# fenrir.net
KiCad netlist of a schematic drawn in EAGLE
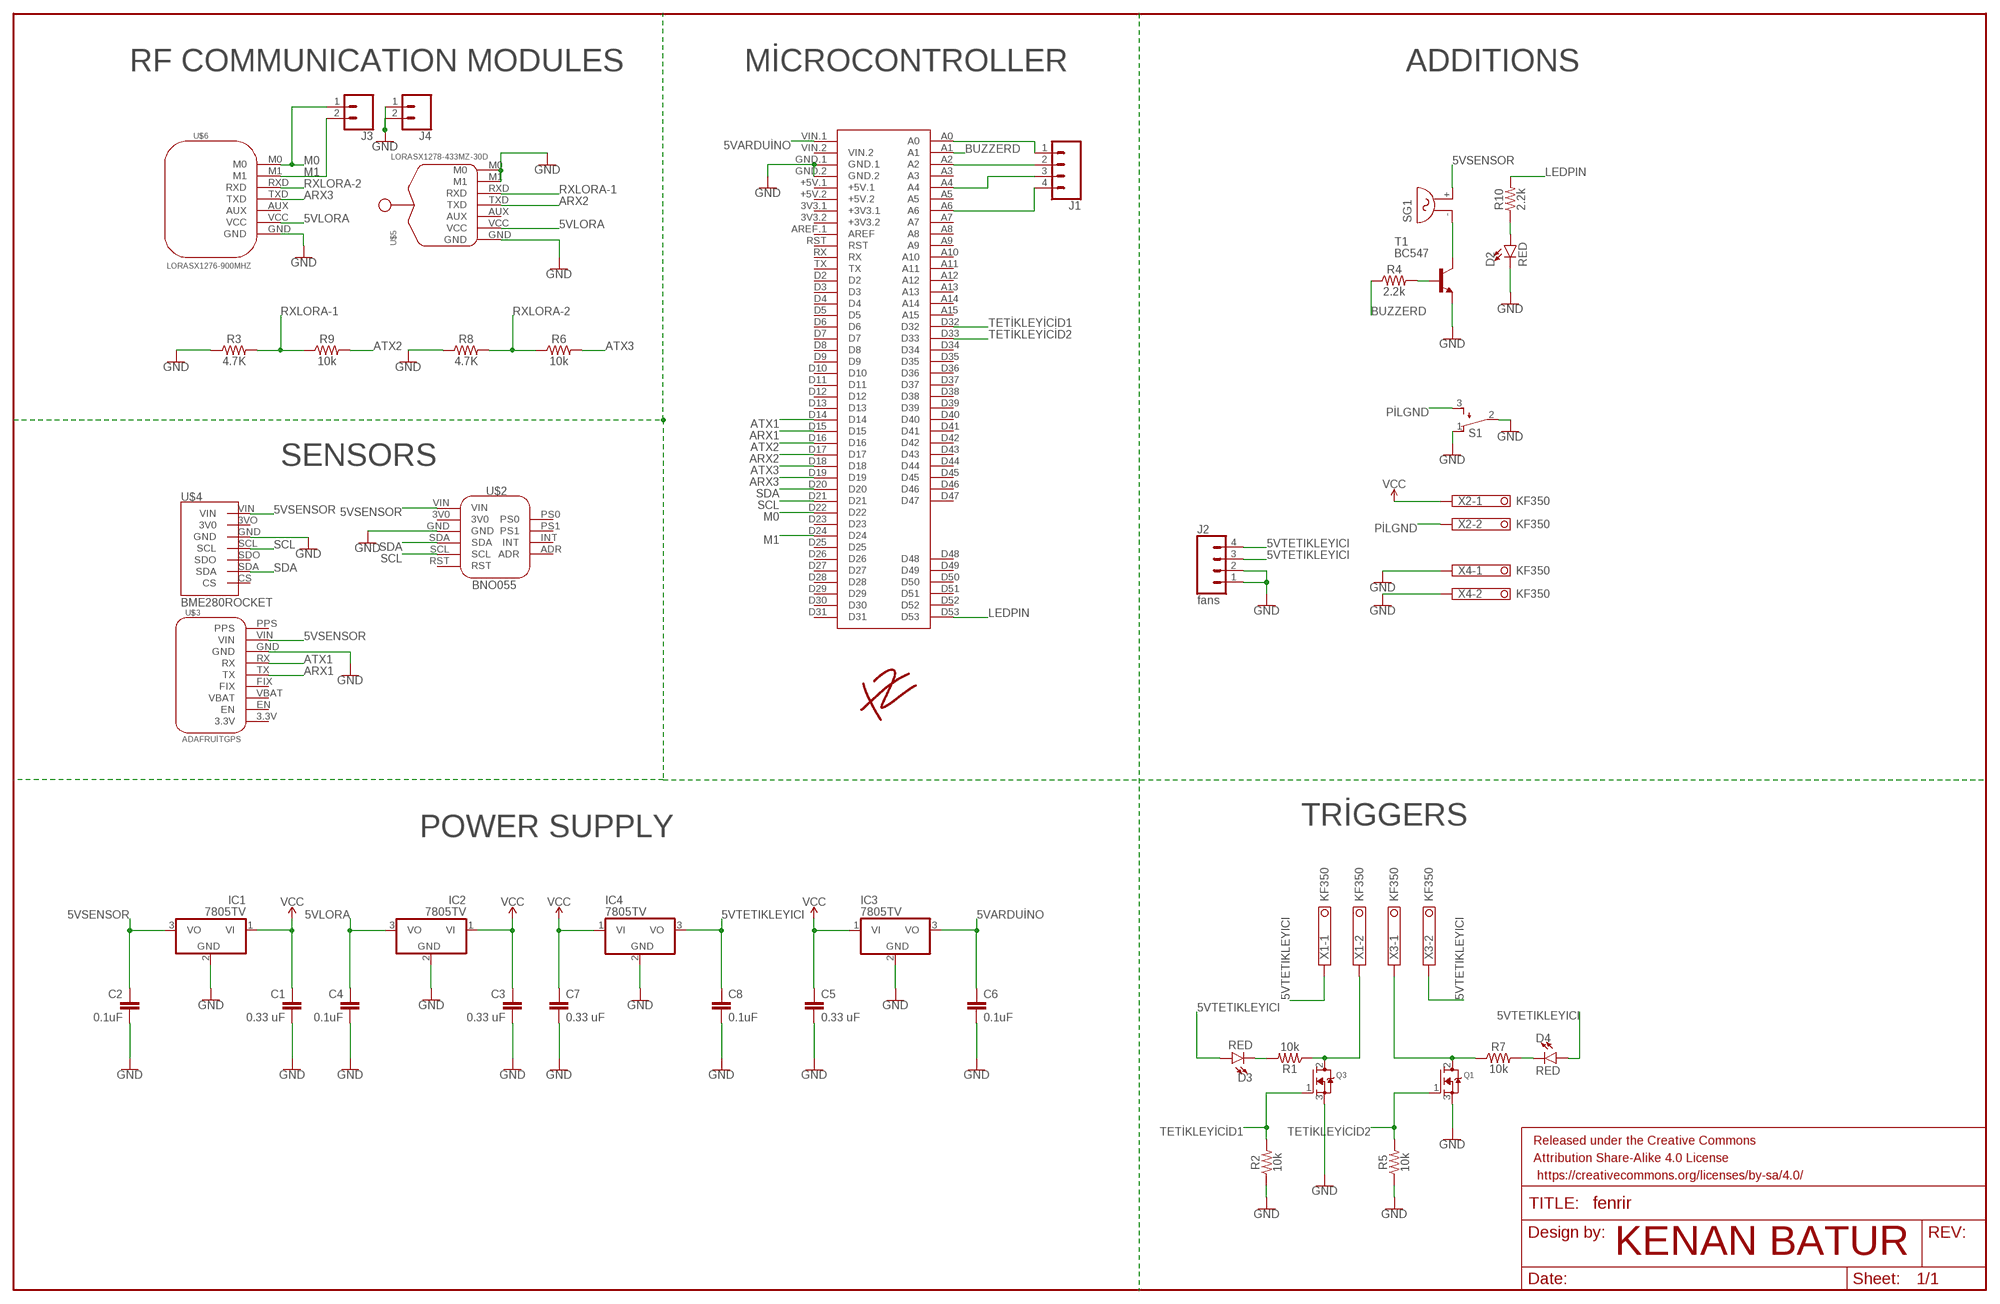
[diagram p0: schematic, sheet 1]

(export (version "E")
  (design (tool "Eeschema 10.0.6"))
  (components
    (comp (ref "C1")
      (value "0.33 uF")
      (footprint "eagle-import:C2.5-3")
      (libsource (lib "eagle-import") (part "C2,5-3"))
    )
    (comp (ref "C2")
      (value "0.1uF")
      (footprint "eagle-import:C2.5-3")
      (libsource (lib "eagle-import") (part "C2,5-3"))
    )
    (comp (ref "C3")
      (value "0.33 uF")
      (footprint "eagle-import:C2.5-3")
      (libsource (lib "eagle-import") (part "C2,5-3"))
    )
    (comp (ref "C4")
      (value "0.1uF")
      (footprint "eagle-import:C2.5-3")
      (libsource (lib "eagle-import") (part "C2,5-3"))
    )
    (comp (ref "C5")
      (value "0.33 uF")
      (footprint "eagle-import:C2.5-3")
      (libsource (lib "eagle-import") (part "C2,5-3"))
    )
    (comp (ref "C6")
      (value "0.1uF")
      (footprint "eagle-import:C2.5-3")
      (libsource (lib "eagle-import") (part "C2,5-3"))
    )
    (comp (ref "C7")
      (value "0.33 uF")
      (footprint "eagle-import:C2.5-3")
      (libsource (lib "eagle-import") (part "C2,5-3"))
    )
    (comp (ref "C8")
      (value "0.1uF")
      (footprint "eagle-import:C2.5-3")
      (libsource (lib "eagle-import") (part "C2,5-3"))
    )
    (comp (ref "D2")
      (value "RED")
      (footprint "eagle-import:LED-1206")
      (libsource (lib "eagle-import") (part "LED-RED1206"))
    )
    (comp (ref "D3")
      (value "RED")
      (footprint "eagle-import:LED-1206")
      (libsource (lib "eagle-import") (part "LED-RED1206"))
    )
    (comp (ref "D4")
      (value "RED")
      (footprint "eagle-import:LED-1206")
      (libsource (lib "eagle-import") (part "LED-RED1206"))
    )
    (comp (ref "FRAME2")
      (value "FRAME-LEDGER")
      (footprint "eagle-import:CREATIVE_COMMONS")
      (fields (field (name "DESIGN") "asd"))
      (libsource (lib "eagle-import") (part "FRAME-LEDGER"))
    )
    (comp (ref "IC1")
      (value "7805TV")
      (footprint "eagle-import:TO220V")
      (libsource (lib "eagle-import") (part "78TV05"))
    )
    (comp (ref "IC2")
      (value "7805TV")
      (footprint "eagle-import:TO220V")
      (libsource (lib "eagle-import") (part "78TV05"))
    )
    (comp (ref "IC3")
      (value "7805TV")
      (footprint "eagle-import:TO220V")
      (libsource (lib "eagle-import") (part "78TV05"))
    )
    (comp (ref "IC4")
      (value "7805TV")
      (footprint "eagle-import:TO220V")
      (libsource (lib "eagle-import") (part "78TV05"))
    )
    (comp (ref "J1")
      (value "CONN_04")
      (footprint "eagle-import:1X04")
      (libsource (lib "eagle-import") (part "CONN_04"))
    )
    (comp (ref "J2")
      (value "fans")
      (footprint "eagle-import:1X04")
      (libsource (lib "eagle-import") (part "CONN_04"))
    )
    (comp (ref "J3")
      (value "CONN_02")
      (footprint "eagle-import:1X02")
      (libsource (lib "eagle-import") (part "CONN_02"))
    )
    (comp (ref "J4")
      (value "CONN_02")
      (footprint "eagle-import:1X02")
      (libsource (lib "eagle-import") (part "CONN_02"))
    )
    (comp (ref "Q1")
      (value "MOSFET-NGDS_TO220V")
      (footprint "eagle-import:TO220V")
      (libsource (lib "eagle-import") (part "MOSFET-NGDS_TO220V"))
    )
    (comp (ref "Q3")
      (value "MOSFET-NGDS_TO220V")
      (footprint "eagle-import:TO220V")
      (libsource (lib "eagle-import") (part "MOSFET-NGDS_TO220V"))
    )
    (comp (ref "R1")
      (value "10k")
      (footprint "eagle-import:AXIAL-0.3")
      (libsource (lib "eagle-import") (part "10KOHM-HORIZ-1/4W-1%"))
    )
    (comp (ref "R2")
      (value "10k")
      (footprint "eagle-import:AXIAL-0.3")
      (libsource (lib "eagle-import") (part "10KOHM-HORIZ-1/4W-1%"))
    )
    (comp (ref "R3")
      (value "4.7K")
      (footprint "eagle-import:AXIAL-0.3")
      (libsource (lib "eagle-import") (part "10KOHM-HORIZ-1/4W-5%"))
    )
    (comp (ref "R4")
      (value "2.2k")
      (footprint "eagle-import:AXIAL-0.3")
      (libsource (lib "eagle-import") (part "10KOHM-HORIZ-1/4W-1%"))
    )
    (comp (ref "R5")
      (value "10k")
      (footprint "eagle-import:AXIAL-0.3")
      (libsource (lib "eagle-import") (part "10KOHM-HORIZ-1/4W-1%"))
    )
    (comp (ref "R6")
      (value "10k")
      (footprint "eagle-import:AXIAL-0.3")
      (libsource (lib "eagle-import") (part "10KOHM-HORIZ-1/4W-5%"))
    )
    (comp (ref "R7")
      (value "10k")
      (footprint "eagle-import:AXIAL-0.3")
      (libsource (lib "eagle-import") (part "10KOHM-HORIZ-1/4W-1%"))
    )
    (comp (ref "R8")
      (value "4.7K")
      (footprint "eagle-import:AXIAL-0.3")
      (libsource (lib "eagle-import") (part "10KOHM-HORIZ-1/4W-5%"))
    )
    (comp (ref "R9")
      (value "10k")
      (footprint "eagle-import:AXIAL-0.3")
      (libsource (lib "eagle-import") (part "10KOHM-HORIZ-1/4W-5%"))
    )
    (comp (ref "R10")
      (value "2.2k")
      (footprint "eagle-import:AXIAL-0.3")
      (libsource (lib "eagle-import") (part "10KOHM-HORIZ-1/4W-1%"))
    )
    (comp (ref "S1")
      (value "TL32PO")
      (footprint "eagle-import:TL3XPO")
      (libsource (lib "eagle-import") (part "TL32PO"))
    )
    (comp (ref "SG1")
      (value "F/QMX")
      (footprint "eagle-import:F_QMX")
      (libsource (lib "eagle-import") (part "F/QMX"))
    )
    (comp (ref "T1")
      (value "BC547")
      (footprint "eagle-import:TO92")
      (libsource (lib "eagle-import") (part "BC547"))
    )
    (comp (ref "U$1")
      (value "MEGA2560_MIKRO")
      (footprint "eagle-import:MEGA2560_MIKRO")
      (libsource (lib "eagle-import") (part "MEGA2560_MIKRO"))
    )
    (comp (ref "U$2")
      (value "BNO055")
      (footprint "eagle-import:BNO055")
      (libsource (lib "eagle-import") (part "BNO055"))
    )
    (comp (ref "U$3")
      (value "ADAFRUİTGPS")
      (footprint "eagle-import:ADAFRUİTGPS")
      (libsource (lib "eagle-import") (part "ADAFRUİTGPS"))
    )
    (comp (ref "U$4")
      (value "BME280ROCKET")
      (footprint "eagle-import:BME280ROCKET")
      (libsource (lib "eagle-import") (part "BME280ROCKET"))
    )
    (comp (ref "U$5")
      (value "LORASX1278-433MZ-30D")
      (footprint "eagle-import:LORASX1278-433MHZ-30D")
      (libsource (lib "eagle-import") (part "LORASX1278-433MZ-30D"))
    )
    (comp (ref "U$6")
      (value "LORASX1276-900MHZ")
      (footprint "eagle-import:LORASX1278-433MHZ")
      (libsource (lib "eagle-import") (part "LORASX1278-433MHZ"))
    )
    (comp (ref "U$7")
      (value "MAVİLOGO")
      (footprint "eagle-import:LOGOMAVİ")
      (libsource (lib "eagle-import") (part "MAVİLOGO"))
    )
    (comp (ref "X1")
      (value "KF350")
      (footprint "eagle-import:TERMINAL-BLOCK-2-PIN-3.5MM-ROUND-PAD")
      (libsource (lib "eagle-import") (part "TERMINAL-BLOCK-3.5MM-2-PIN-ROUND-PAD"))
    )
    (comp (ref "X2")
      (value "KF350")
      (footprint "eagle-import:TERMINAL-BLOCK-2-PIN-3.5MM-ROUND-PAD")
      (libsource (lib "eagle-import") (part "TERMINAL-BLOCK-3.5MM-2-PIN-ROUND-PAD"))
    )
    (comp (ref "X3")
      (value "KF350")
      (footprint "eagle-import:TERMINAL-BLOCK-2-PIN-3.5MM-ROUND-PAD")
      (libsource (lib "eagle-import") (part "TERMINAL-BLOCK-3.5MM-2-PIN-ROUND-PAD"))
    )
    (comp (ref "X4")
      (value "KF350")
      (footprint "eagle-import:TERMINAL-BLOCK-2-PIN-3.5MM-ROUND-PAD")
      (libsource (lib "eagle-import") (part "TERMINAL-BLOCK-3.5MM-2-PIN-ROUND-PAD"))
    )
  )
  (nets
    (net (code "1") (name "/5VARDUİNO") (class "Default")
      (node (ref "C6") (pin "1") (pinfunction "1_1") (pintype "passive"))
      (node (ref "IC3") (pin "3") (pinfunction "VO_3") (pintype "passive"))
      (node (ref "U$1") (pin "VIN.1") (pinfunction "VIN.1_VIN.1") (pintype "bidirectional"))
    )
    (net (code "2") (name "/5VLORA") (class "Default")
      (node (ref "C4") (pin "1") (pinfunction "1_1") (pintype "passive"))
      (node (ref "IC2") (pin "3") (pinfunction "VO_3") (pintype "passive"))
      (node (ref "U$5") (pin "VCC") (pinfunction "VCC_VCC") (pintype "bidirectional"))
      (node (ref "U$6") (pin "VCC") (pinfunction "VCC_VCC") (pintype "bidirectional"))
    )
    (net (code "3") (name "/5VSENSOR") (class "Default")
      (node (ref "C2") (pin "1") (pinfunction "1_1") (pintype "passive"))
      (node (ref "IC1") (pin "3") (pinfunction "VO_3") (pintype "passive"))
      (node (ref "SG1") (pin "+") (pinfunction "2_+") (pintype "passive"))
      (node (ref "U$2") (pin "VIN") (pinfunction "VIN_VIN") (pintype "bidirectional"))
      (node (ref "U$3") (pin "VIN") (pinfunction "VIN_VIN") (pintype "bidirectional"))
      (node (ref "U$4") (pin "VIN") (pinfunction "VIN_VIN") (pintype "bidirectional"))
    )
    (net (code "4") (name "/5VTETIKLEYICI") (class "Default")
      (node (ref "C8") (pin "1") (pinfunction "1_1") (pintype "passive"))
      (node (ref "D3") (pin "A") (pinfunction "A_A") (pintype "passive"))
      (node (ref "D4") (pin "A") (pinfunction "A_A") (pintype "passive"))
      (node (ref "IC4") (pin "3") (pinfunction "VO_3") (pintype "passive"))
      (node (ref "J2") (pin "3") (pinfunction "3_3") (pintype "passive"))
      (node (ref "J2") (pin "4") (pinfunction "4_4") (pintype "passive"))
      (node (ref "X1") (pin "1") (pinfunction "K_1") (pintype "passive"))
      (node (ref "X3") (pin "2") (pinfunction "K_2") (pintype "passive"))
    )
    (net (code "5") (name "/ARX1") (class "Default")
      (node (ref "U$1") (pin "D15") (pinfunction "D15_D15") (pintype "bidirectional"))
      (node (ref "U$3") (pin "TX") (pinfunction "TX_TX") (pintype "bidirectional"))
    )
    (net (code "6") (name "/ARX2") (class "Default")
      (node (ref "U$1") (pin "D17") (pinfunction "D17_D17") (pintype "bidirectional"))
      (node (ref "U$5") (pin "TXD") (pinfunction "TXD_TXD") (pintype "bidirectional"))
    )
    (net (code "7") (name "/ARX3") (class "Default")
      (node (ref "U$1") (pin "D19") (pinfunction "D19_D19") (pintype "bidirectional"))
      (node (ref "U$6") (pin "TXD") (pinfunction "TXD_TXD") (pintype "bidirectional"))
    )
    (net (code "8") (name "/ATX1") (class "Default")
      (node (ref "U$1") (pin "D14") (pinfunction "D14_D14") (pintype "bidirectional"))
      (node (ref "U$3") (pin "RX") (pinfunction "RX_RX") (pintype "bidirectional"))
    )
    (net (code "9") (name "/ATX2") (class "Default")
      (node (ref "R9") (pin "P$2") (pinfunction "2_P$2") (pintype "passive"))
      (node (ref "U$1") (pin "D16") (pinfunction "D16_D16") (pintype "bidirectional"))
    )
    (net (code "10") (name "/ATX3") (class "Default")
      (node (ref "R6") (pin "P$2") (pinfunction "2_P$2") (pintype "passive"))
      (node (ref "U$1") (pin "D18") (pinfunction "D18_D18") (pintype "bidirectional"))
    )
    (net (code "11") (name "/BUZZERD") (class "Default")
      (node (ref "R4") (pin "P$1") (pinfunction "1_P$1") (pintype "passive"))
      (node (ref "U$1") (pin "A1") (pinfunction "A1_A1") (pintype "bidirectional"))
    )
    (net (code "12") (name "/LEDPIN") (class "Default")
      (node (ref "R10") (pin "P$2") (pinfunction "2_P$2") (pintype "passive"))
      (node (ref "U$1") (pin "D53") (pinfunction "D53_D53") (pintype "bidirectional"))
    )
    (net (code "13") (name "/M0") (class "Default")
      (node (ref "J3") (pin "1") (pinfunction "1_1") (pintype "passive"))
      (node (ref "U$1") (pin "D22") (pinfunction "D22_D22") (pintype "bidirectional"))
      (node (ref "U$6") (pin "M0") (pinfunction "M0_M0") (pintype "bidirectional"))
    )
    (net (code "14") (name "/M1") (class "Default")
      (node (ref "J3") (pin "2") (pinfunction "2_2") (pintype "passive"))
      (node (ref "U$1") (pin "D24") (pinfunction "D24_D24") (pintype "bidirectional"))
      (node (ref "U$6") (pin "M1") (pinfunction "M1_M1") (pintype "bidirectional"))
    )
    (net (code "15") (name "/PİLGND") (class "Default")
      (node (ref "S1") (pin "3") (pinfunction "S_3") (pintype "passive"))
      (node (ref "X2") (pin "2") (pinfunction "K_2") (pintype "passive"))
    )
    (net (code "16") (name "/RXLORA-1") (class "Default")
      (node (ref "R3") (pin "P$2") (pinfunction "2_P$2") (pintype "passive"))
      (node (ref "R9") (pin "P$1") (pinfunction "1_P$1") (pintype "passive"))
      (node (ref "U$5") (pin "RXD") (pinfunction "RXD_RXD") (pintype "bidirectional"))
    )
    (net (code "17") (name "/RXLORA-2") (class "Default")
      (node (ref "R6") (pin "P$1") (pinfunction "1_P$1") (pintype "passive"))
      (node (ref "R8") (pin "P$2") (pinfunction "2_P$2") (pintype "passive"))
      (node (ref "U$6") (pin "RXD") (pinfunction "RXD_RXD") (pintype "bidirectional"))
    )
    (net (code "18") (name "/SCL") (class "Default")
      (node (ref "U$1") (pin "D21") (pinfunction "D21_D21") (pintype "bidirectional"))
      (node (ref "U$2") (pin "SCL") (pinfunction "SCL_SCL") (pintype "bidirectional"))
      (node (ref "U$4") (pin "SCL") (pinfunction "SCL_SCL") (pintype "bidirectional"))
    )
    (net (code "19") (name "/SDA") (class "Default")
      (node (ref "U$1") (pin "D20") (pinfunction "D20_D20") (pintype "bidirectional"))
      (node (ref "U$2") (pin "SDA") (pinfunction "SDA_SDA") (pintype "bidirectional"))
      (node (ref "U$4") (pin "SDA") (pinfunction "SDA_SDA") (pintype "bidirectional"))
    )
    (net (code "20") (name "/TETİKLEYİCİD1") (class "Default")
      (node (ref "Q3") (pin "1") (pinfunction "G_1") (pintype "bidirectional"))
      (node (ref "R2") (pin "P$2") (pinfunction "2_P$2") (pintype "passive"))
      (node (ref "U$1") (pin "D32") (pinfunction "D32_D32") (pintype "bidirectional"))
    )
    (net (code "21") (name "/TETİKLEYİCİD2") (class "Default")
      (node (ref "Q1") (pin "1") (pinfunction "G_1") (pintype "bidirectional"))
      (node (ref "R5") (pin "P$2") (pinfunction "2_P$2") (pintype "passive"))
      (node (ref "U$1") (pin "D33") (pinfunction "D33_D33") (pintype "bidirectional"))
    )
    (net (code "22") (name "GND") (class "Default")
      (node (ref "C1") (pin "2") (pinfunction "2_2") (pintype "passive"))
      (node (ref "C2") (pin "2") (pinfunction "2_2") (pintype "passive"))
      (node (ref "C3") (pin "2") (pinfunction "2_2") (pintype "passive"))
      (node (ref "C4") (pin "2") (pinfunction "2_2") (pintype "passive"))
      (node (ref "C5") (pin "2") (pinfunction "2_2") (pintype "passive"))
      (node (ref "C6") (pin "2") (pinfunction "2_2") (pintype "passive"))
      (node (ref "C7") (pin "2") (pinfunction "2_2") (pintype "passive"))
      (node (ref "C8") (pin "2") (pinfunction "2_2") (pintype "passive"))
      (node (ref "D2") (pin "C") (pinfunction "C_C") (pintype "passive"))
      (node (ref "IC1") (pin "2") (pinfunction "GND_2") (pintype "passive"))
      (node (ref "IC2") (pin "2") (pinfunction "GND_2") (pintype "passive"))
      (node (ref "IC3") (pin "2") (pinfunction "GND_2") (pintype "passive"))
      (node (ref "IC4") (pin "2") (pinfunction "GND_2") (pintype "passive"))
      (node (ref "J2") (pin "1") (pinfunction "1_1") (pintype "passive"))
      (node (ref "J2") (pin "2") (pinfunction "2_2") (pintype "passive"))
      (node (ref "J4") (pin "1") (pinfunction "1_1") (pintype "passive"))
      (node (ref "J4") (pin "2") (pinfunction "2_2") (pintype "passive"))
      (node (ref "Q1") (pin "3") (pinfunction "S_3") (pintype "bidirectional"))
      (node (ref "Q3") (pin "3") (pinfunction "S_3") (pintype "bidirectional"))
      (node (ref "R2") (pin "P$1") (pinfunction "1_P$1") (pintype "passive"))
      (node (ref "R3") (pin "P$1") (pinfunction "1_P$1") (pintype "passive"))
      (node (ref "R5") (pin "P$1") (pinfunction "1_P$1") (pintype "passive"))
      (node (ref "R8") (pin "P$1") (pinfunction "1_P$1") (pintype "passive"))
      (node (ref "S1") (pin "1") (pinfunction "O_1") (pintype "passive"))
      (node (ref "S1") (pin "2") (pinfunction "P_2") (pintype "passive"))
      (node (ref "T1") (pin "1") (pinfunction "E_1") (pintype "passive"))
      (node (ref "U$1") (pin "GND.1") (pinfunction "GND.1_GND.1") (pintype "bidirectional"))
      (node (ref "U$1") (pin "GND.2") (pinfunction "GND.2_GND.2") (pintype "bidirectional"))
      (node (ref "U$2") (pin "GND") (pinfunction "GND_GND") (pintype "bidirectional"))
      (node (ref "U$3") (pin "GND") (pinfunction "GND_GND") (pintype "bidirectional"))
      (node (ref "U$4") (pin "GND") (pinfunction "GND_GND") (pintype "bidirectional"))
      (node (ref "U$5") (pin "GND") (pinfunction "GND_GND") (pintype "bidirectional"))
      (node (ref "U$5") (pin "M0") (pinfunction "M0_M0") (pintype "bidirectional"))
      (node (ref "U$5") (pin "M1") (pinfunction "M1_M1") (pintype "bidirectional"))
      (node (ref "U$6") (pin "GND") (pinfunction "GND_GND") (pintype "bidirectional"))
      (node (ref "X4") (pin "1") (pinfunction "K_1") (pintype "passive"))
      (node (ref "X4") (pin "2") (pinfunction "K_2") (pintype "passive"))
    )
    (net (code "23") (name "Net-(J1-Pad1)") (class "Default")
      (node (ref "J1") (pin "1") (pinfunction "1_1") (pintype "passive"))
      (node (ref "U$1") (pin "A0") (pinfunction "A0_A0") (pintype "bidirectional"))
    )
    (net (code "24") (name "Net-(J1-Pad2)") (class "Default")
      (node (ref "J1") (pin "2") (pinfunction "2_2") (pintype "passive"))
      (node (ref "U$1") (pin "A2") (pinfunction "A2_A2") (pintype "bidirectional"))
    )
    (net (code "25") (name "Net-(J1-Pad3)") (class "Default")
      (node (ref "J1") (pin "3") (pinfunction "3_3") (pintype "passive"))
      (node (ref "U$1") (pin "A4") (pinfunction "A4_A4") (pintype "bidirectional"))
    )
    (net (code "26") (name "Net-(J1-Pad4)") (class "Default")
      (node (ref "J1") (pin "4") (pinfunction "4_4") (pintype "passive"))
      (node (ref "U$1") (pin "A6") (pinfunction "A6_A6") (pintype "bidirectional"))
    )
    (net (code "27") (name "Net-(Q1-D)") (class "Default")
      (node (ref "Q1") (pin "2") (pinfunction "D_2") (pintype "bidirectional"))
      (node (ref "R7") (pin "P$1") (pinfunction "1_P$1") (pintype "passive"))
      (node (ref "X3") (pin "1") (pinfunction "K_1") (pintype "passive"))
    )
    (net (code "28") (name "Net-(Q3-D)") (class "Default")
      (node (ref "Q3") (pin "2") (pinfunction "D_2") (pintype "bidirectional"))
      (node (ref "R1") (pin "P$1") (pinfunction "1_P$1") (pintype "passive"))
      (node (ref "X1") (pin "2") (pinfunction "K_2") (pintype "passive"))
    )
    (net (code "29") (name "Net-(R1-2)") (class "Default")
      (node (ref "D3") (pin "C") (pinfunction "C_C") (pintype "passive"))
      (node (ref "R1") (pin "P$2") (pinfunction "2_P$2") (pintype "passive"))
    )
    (net (code "30") (name "Net-(R4-2)") (class "Default")
      (node (ref "R4") (pin "P$2") (pinfunction "2_P$2") (pintype "passive"))
      (node (ref "T1") (pin "2") (pinfunction "B_2") (pintype "passive"))
    )
    (net (code "31") (name "Net-(R7-2)") (class "Default")
      (node (ref "D4") (pin "C") (pinfunction "C_C") (pintype "passive"))
      (node (ref "R7") (pin "P$2") (pinfunction "2_P$2") (pintype "passive"))
    )
    (net (code "32") (name "Net-(R10-1)") (class "Default")
      (node (ref "D2") (pin "A") (pinfunction "A_A") (pintype "passive"))
      (node (ref "R10") (pin "P$1") (pinfunction "1_P$1") (pintype "passive"))
    )
    (net (code "33") (name "Net-(SG1-1)") (class "Default")
      (node (ref "SG1") (pin "-") (pinfunction "1_-") (pintype "passive"))
      (node (ref "T1") (pin "3") (pinfunction "C_3") (pintype "passive"))
    )
    (net (code "34") (name "VCC") (class "Default")
      (node (ref "C1") (pin "1") (pinfunction "1_1") (pintype "passive"))
      (node (ref "C3") (pin "1") (pinfunction "1_1") (pintype "passive"))
      (node (ref "C5") (pin "1") (pinfunction "1_1") (pintype "passive"))
      (node (ref "C7") (pin "1") (pinfunction "1_1") (pintype "passive"))
      (node (ref "IC1") (pin "1") (pinfunction "VI_1") (pintype "input"))
      (node (ref "IC2") (pin "1") (pinfunction "VI_1") (pintype "input"))
      (node (ref "IC3") (pin "1") (pinfunction "VI_1") (pintype "input"))
      (node (ref "IC4") (pin "1") (pinfunction "VI_1") (pintype "input"))
      (node (ref "X2") (pin "1") (pinfunction "K_1") (pintype "passive"))
    )
    (net (code "35") (name "unconnected-(U$1-+3V3.1-Pad3V3.1)") (class "Default")
      (node (ref "U$1") (pin "3V3.1") (pinfunction "+3V3.1_3V3.1") (pintype "bidirectional"))
    )
    (net (code "36") (name "unconnected-(U$1-+3V3.2-Pad3V3.2)") (class "Default")
      (node (ref "U$1") (pin "3V3.2") (pinfunction "+3V3.2_3V3.2") (pintype "bidirectional"))
    )
    (net (code "37") (name "unconnected-(U$1-AREF-PadAREF.1)") (class "Default")
      (node (ref "U$1") (pin "AREF.1") (pinfunction "AREF_AREF.1") (pintype "bidirectional"))
    )
    (net (code "38") (name "unconnected-(U$1-Pad+5V.1)") (class "Default")
      (node (ref "U$1") (pin "+5V.1") (pinfunction "+5V.1_+5V.1") (pintype "bidirectional"))
    )
    (net (code "39") (name "unconnected-(U$1-Pad+5V.2)") (class "Default")
      (node (ref "U$1") (pin "+5V.2") (pinfunction "+5V.2_+5V.2") (pintype "bidirectional"))
    )
    (net (code "40") (name "unconnected-(U$1-PadA3)") (class "Default")
      (node (ref "U$1") (pin "A3") (pinfunction "A3_A3") (pintype "bidirectional"))
    )
    (net (code "41") (name "unconnected-(U$1-PadA5)") (class "Default")
      (node (ref "U$1") (pin "A5") (pinfunction "A5_A5") (pintype "bidirectional"))
    )
    (net (code "42") (name "unconnected-(U$1-PadA7)") (class "Default")
      (node (ref "U$1") (pin "A7") (pinfunction "A7_A7") (pintype "bidirectional"))
    )
    (net (code "43") (name "unconnected-(U$1-PadA8)") (class "Default")
      (node (ref "U$1") (pin "A8") (pinfunction "A8_A8") (pintype "bidirectional"))
    )
    (net (code "44") (name "unconnected-(U$1-PadA9)") (class "Default")
      (node (ref "U$1") (pin "A9") (pinfunction "A9_A9") (pintype "bidirectional"))
    )
    (net (code "45") (name "unconnected-(U$1-PadA10)") (class "Default")
      (node (ref "U$1") (pin "A10") (pinfunction "A10_A10") (pintype "bidirectional"))
    )
    (net (code "46") (name "unconnected-(U$1-PadA11)") (class "Default")
      (node (ref "U$1") (pin "A11") (pinfunction "A11_A11") (pintype "bidirectional"))
    )
    (net (code "47") (name "unconnected-(U$1-PadA12)") (class "Default")
      (node (ref "U$1") (pin "A12") (pinfunction "A12_A12") (pintype "bidirectional"))
    )
    (net (code "48") (name "unconnected-(U$1-PadA13)") (class "Default")
      (node (ref "U$1") (pin "A13") (pinfunction "A13_A13") (pintype "bidirectional"))
    )
    (net (code "49") (name "unconnected-(U$1-PadA14)") (class "Default")
      (node (ref "U$1") (pin "A14") (pinfunction "A14_A14") (pintype "bidirectional"))
    )
    (net (code "50") (name "unconnected-(U$1-PadA15)") (class "Default")
      (node (ref "U$1") (pin "A15") (pinfunction "A15_A15") (pintype "bidirectional"))
    )
    (net (code "51") (name "unconnected-(U$1-PadD2)") (class "Default")
      (node (ref "U$1") (pin "D2") (pinfunction "D2_D2") (pintype "bidirectional"))
    )
    (net (code "52") (name "unconnected-(U$1-PadD3)") (class "Default")
      (node (ref "U$1") (pin "D3") (pinfunction "D3_D3") (pintype "bidirectional"))
    )
    (net (code "53") (name "unconnected-(U$1-PadD4)") (class "Default")
      (node (ref "U$1") (pin "D4") (pinfunction "D4_D4") (pintype "bidirectional"))
    )
    (net (code "54") (name "unconnected-(U$1-PadD5)") (class "Default")
      (node (ref "U$1") (pin "D5") (pinfunction "D5_D5") (pintype "bidirectional"))
    )
    (net (code "55") (name "unconnected-(U$1-PadD6)") (class "Default")
      (node (ref "U$1") (pin "D6") (pinfunction "D6_D6") (pintype "bidirectional"))
    )
    (net (code "56") (name "unconnected-(U$1-PadD7)") (class "Default")
      (node (ref "U$1") (pin "D7") (pinfunction "D7_D7") (pintype "bidirectional"))
    )
    (net (code "57") (name "unconnected-(U$1-PadD8)") (class "Default")
      (node (ref "U$1") (pin "D8") (pinfunction "D8_D8") (pintype "bidirectional"))
    )
    (net (code "58") (name "unconnected-(U$1-PadD9)") (class "Default")
      (node (ref "U$1") (pin "D9") (pinfunction "D9_D9") (pintype "bidirectional"))
    )
    (net (code "59") (name "unconnected-(U$1-PadD10)") (class "Default")
      (node (ref "U$1") (pin "D10") (pinfunction "D10_D10") (pintype "bidirectional"))
    )
    (net (code "60") (name "unconnected-(U$1-PadD11)") (class "Default")
      (node (ref "U$1") (pin "D11") (pinfunction "D11_D11") (pintype "bidirectional"))
    )
    (net (code "61") (name "unconnected-(U$1-PadD12)") (class "Default")
      (node (ref "U$1") (pin "D12") (pinfunction "D12_D12") (pintype "bidirectional"))
    )
    (net (code "62") (name "unconnected-(U$1-PadD13)") (class "Default")
      (node (ref "U$1") (pin "D13") (pinfunction "D13_D13") (pintype "bidirectional"))
    )
    (net (code "63") (name "unconnected-(U$1-PadD23)") (class "Default")
      (node (ref "U$1") (pin "D23") (pinfunction "D23_D23") (pintype "bidirectional"))
    )
    (net (code "64") (name "unconnected-(U$1-PadD25)") (class "Default")
      (node (ref "U$1") (pin "D25") (pinfunction "D25_D25") (pintype "bidirectional"))
    )
    (net (code "65") (name "unconnected-(U$1-PadD26)") (class "Default")
      (node (ref "U$1") (pin "D26") (pinfunction "D26_D26") (pintype "bidirectional"))
    )
    (net (code "66") (name "unconnected-(U$1-PadD27)") (class "Default")
      (node (ref "U$1") (pin "D27") (pinfunction "D27_D27") (pintype "bidirectional"))
    )
    (net (code "67") (name "unconnected-(U$1-PadD28)") (class "Default")
      (node (ref "U$1") (pin "D28") (pinfunction "D28_D28") (pintype "bidirectional"))
    )
    (net (code "68") (name "unconnected-(U$1-PadD29)") (class "Default")
      (node (ref "U$1") (pin "D29") (pinfunction "D29_D29") (pintype "bidirectional"))
    )
    (net (code "69") (name "unconnected-(U$1-PadD30)") (class "Default")
      (node (ref "U$1") (pin "D30") (pinfunction "D30_D30") (pintype "bidirectional"))
    )
    (net (code "70") (name "unconnected-(U$1-PadD31)") (class "Default")
      (node (ref "U$1") (pin "D31") (pinfunction "D31_D31") (pintype "bidirectional"))
    )
    (net (code "71") (name "unconnected-(U$1-PadD34)") (class "Default")
      (node (ref "U$1") (pin "D34") (pinfunction "D34_D34") (pintype "bidirectional"))
    )
    (net (code "72") (name "unconnected-(U$1-PadD35)") (class "Default")
      (node (ref "U$1") (pin "D35") (pinfunction "D35_D35") (pintype "bidirectional"))
    )
    (net (code "73") (name "unconnected-(U$1-PadD36)") (class "Default")
      (node (ref "U$1") (pin "D36") (pinfunction "D36_D36") (pintype "bidirectional"))
    )
    (net (code "74") (name "unconnected-(U$1-PadD37)") (class "Default")
      (node (ref "U$1") (pin "D37") (pinfunction "D37_D37") (pintype "bidirectional"))
    )
    (net (code "75") (name "unconnected-(U$1-PadD38)") (class "Default")
      (node (ref "U$1") (pin "D38") (pinfunction "D38_D38") (pintype "bidirectional"))
    )
    (net (code "76") (name "unconnected-(U$1-PadD39)") (class "Default")
      (node (ref "U$1") (pin "D39") (pinfunction "D39_D39") (pintype "bidirectional"))
    )
    (net (code "77") (name "unconnected-(U$1-PadD40)") (class "Default")
      (node (ref "U$1") (pin "D40") (pinfunction "D40_D40") (pintype "bidirectional"))
    )
    (net (code "78") (name "unconnected-(U$1-PadD41)") (class "Default")
      (node (ref "U$1") (pin "D41") (pinfunction "D41_D41") (pintype "bidirectional"))
    )
    (net (code "79") (name "unconnected-(U$1-PadD42)") (class "Default")
      (node (ref "U$1") (pin "D42") (pinfunction "D42_D42") (pintype "bidirectional"))
    )
    (net (code "80") (name "unconnected-(U$1-PadD43)") (class "Default")
      (node (ref "U$1") (pin "D43") (pinfunction "D43_D43") (pintype "bidirectional"))
    )
    (net (code "81") (name "unconnected-(U$1-PadD44)") (class "Default")
      (node (ref "U$1") (pin "D44") (pinfunction "D44_D44") (pintype "bidirectional"))
    )
    (net (code "82") (name "unconnected-(U$1-PadD45)") (class "Default")
      (node (ref "U$1") (pin "D45") (pinfunction "D45_D45") (pintype "bidirectional"))
    )
    (net (code "83") (name "unconnected-(U$1-PadD46)") (class "Default")
      (node (ref "U$1") (pin "D46") (pinfunction "D46_D46") (pintype "bidirectional"))
    )
    (net (code "84") (name "unconnected-(U$1-PadD47)") (class "Default")
      (node (ref "U$1") (pin "D47") (pinfunction "D47_D47") (pintype "bidirectional"))
    )
    (net (code "85") (name "unconnected-(U$1-PadD48)") (class "Default")
      (node (ref "U$1") (pin "D48") (pinfunction "D48_D48") (pintype "bidirectional"))
    )
    (net (code "86") (name "unconnected-(U$1-PadD49)") (class "Default")
      (node (ref "U$1") (pin "D49") (pinfunction "D49_D49") (pintype "bidirectional"))
    )
    (net (code "87") (name "unconnected-(U$1-PadD50)") (class "Default")
      (node (ref "U$1") (pin "D50") (pinfunction "D50_D50") (pintype "bidirectional"))
    )
    (net (code "88") (name "unconnected-(U$1-PadD51)") (class "Default")
      (node (ref "U$1") (pin "D51") (pinfunction "D51_D51") (pintype "bidirectional"))
    )
    (net (code "89") (name "unconnected-(U$1-PadD52)") (class "Default")
      (node (ref "U$1") (pin "D52") (pinfunction "D52_D52") (pintype "bidirectional"))
    )
    (net (code "90") (name "unconnected-(U$1-PadRST)") (class "Default")
      (node (ref "U$1") (pin "RST") (pinfunction "RST_RST") (pintype "bidirectional"))
    )
    (net (code "91") (name "unconnected-(U$1-PadRX)") (class "Default")
      (node (ref "U$1") (pin "RX") (pinfunction "RX_RX") (pintype "bidirectional"))
    )
    (net (code "92") (name "unconnected-(U$1-PadTX)") (class "Default")
      (node (ref "U$1") (pin "TX") (pinfunction "TX_TX") (pintype "bidirectional"))
    )
    (net (code "93") (name "unconnected-(U$1-PadVIN.2)") (class "Default")
      (node (ref "U$1") (pin "VIN.2") (pinfunction "VIN.2_VIN.2") (pintype "bidirectional"))
    )
    (net (code "94") (name "unconnected-(U$2-Pad3V0)") (class "Default")
      (node (ref "U$2") (pin "3V0") (pinfunction "3V0_3V0") (pintype "bidirectional"))
    )
    (net (code "95") (name "unconnected-(U$2-PadADR)") (class "Default")
      (node (ref "U$2") (pin "ADR") (pinfunction "ADR_ADR") (pintype "bidirectional"))
    )
    (net (code "96") (name "unconnected-(U$2-PadINT)") (class "Default")
      (node (ref "U$2") (pin "INT") (pinfunction "INT_INT") (pintype "bidirectional"))
    )
    (net (code "97") (name "unconnected-(U$2-PadPS0)") (class "Default")
      (node (ref "U$2") (pin "PS0") (pinfunction "PS0_PS0") (pintype "bidirectional"))
    )
    (net (code "98") (name "unconnected-(U$2-PadPS1)") (class "Default")
      (node (ref "U$2") (pin "PS1") (pinfunction "PS1_PS1") (pintype "bidirectional"))
    )
    (net (code "99") (name "unconnected-(U$2-PadRST)") (class "Default")
      (node (ref "U$2") (pin "RST") (pinfunction "RST_RST") (pintype "bidirectional"))
    )
    (net (code "100") (name "unconnected-(U$3-Pad3.3V)") (class "Default")
      (node (ref "U$3") (pin "3.3V") (pinfunction "3.3V_3.3V") (pintype "bidirectional"))
    )
    (net (code "101") (name "unconnected-(U$3-PadEN)") (class "Default")
      (node (ref "U$3") (pin "EN") (pinfunction "EN_EN") (pintype "bidirectional"))
    )
    (net (code "102") (name "unconnected-(U$3-PadFIX)") (class "Default")
      (node (ref "U$3") (pin "FIX") (pinfunction "FIX_FIX") (pintype "bidirectional"))
    )
    (net (code "103") (name "unconnected-(U$3-PadPPS)") (class "Default")
      (node (ref "U$3") (pin "PPS") (pinfunction "PPS_PPS") (pintype "bidirectional"))
    )
    (net (code "104") (name "unconnected-(U$3-PadVBAT)") (class "Default")
      (node (ref "U$3") (pin "VBAT") (pinfunction "VBAT_VBAT") (pintype "bidirectional"))
    )
    (net (code "105") (name "unconnected-(U$4-3V0-Pad3VO)") (class "Default")
      (node (ref "U$4") (pin "3VO") (pinfunction "3V0_3VO") (pintype "bidirectional"))
    )
    (net (code "106") (name "unconnected-(U$4-PadCS)") (class "Default")
      (node (ref "U$4") (pin "CS") (pinfunction "CS_CS") (pintype "bidirectional"))
    )
    (net (code "107") (name "unconnected-(U$4-PadSDO)") (class "Default")
      (node (ref "U$4") (pin "SDO") (pinfunction "SDO_SDO") (pintype "bidirectional"))
    )
    (net (code "108") (name "unconnected-(U$5-PadAUX)") (class "Default")
      (node (ref "U$5") (pin "AUX") (pinfunction "AUX_AUX") (pintype "bidirectional"))
    )
    (net (code "109") (name "unconnected-(U$6-PadAUX)") (class "Default")
      (node (ref "U$6") (pin "AUX") (pinfunction "AUX_AUX") (pintype "bidirectional"))
    )
  )
)
